# Sensors_Actuator_lib.net
KiCad netlist of a schematic drawn in Altium Designer
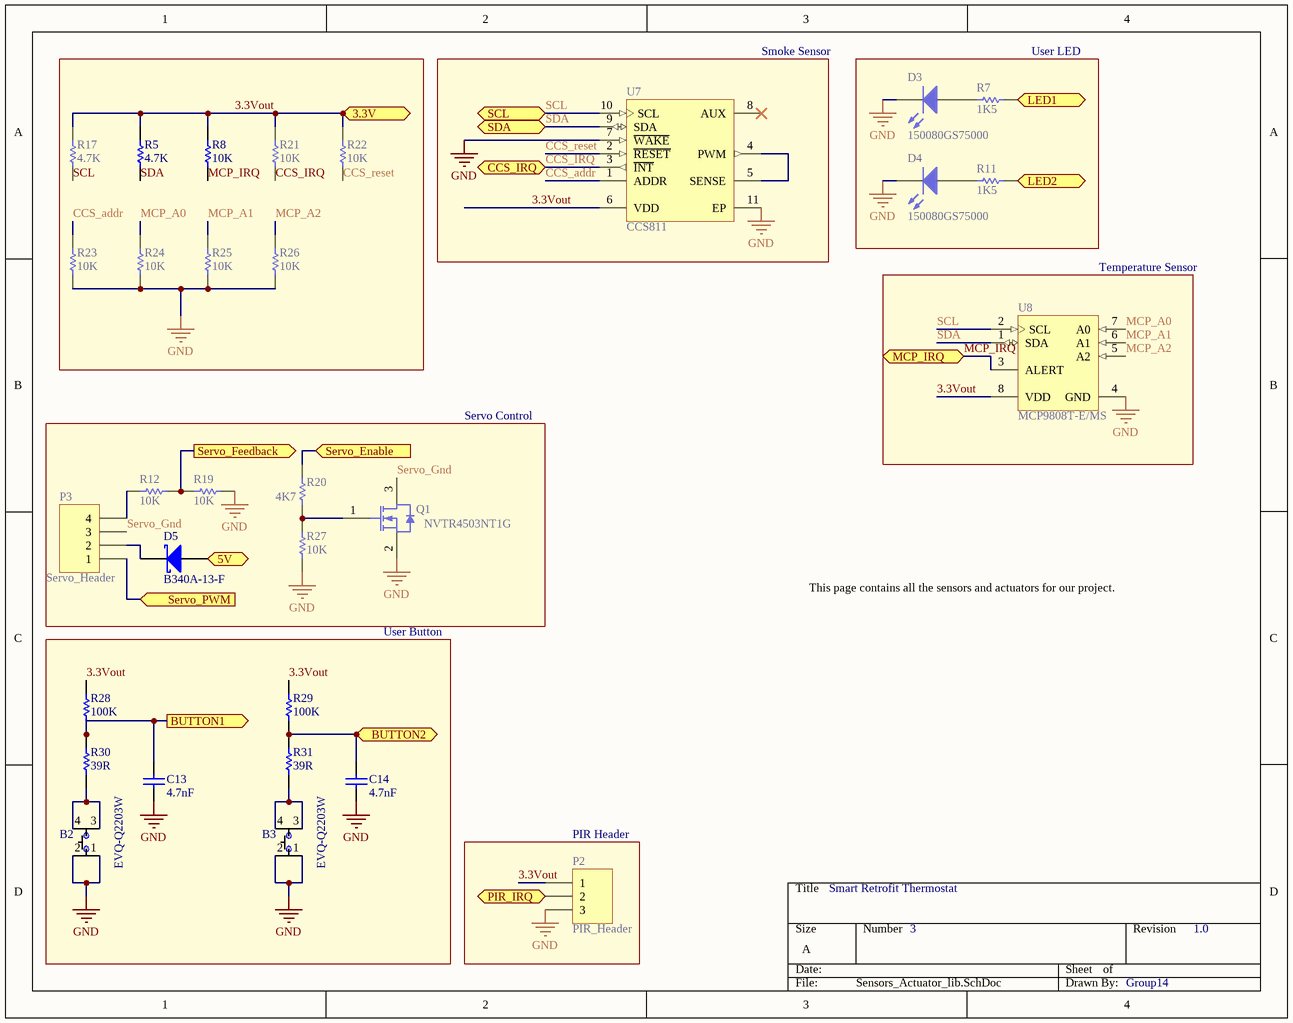
[diagram p0: Sensors_Actuator_lib.SchDoc]

(export (version "E")
  (design (tool "Eeschema 10.0.6"))
  (components
    (comp (ref "B2")
      (value "EVQ-Q2203W")
      (footprint "EVQ-Q2203W")
      (description "SWITCH TACTILE SPST-NO 0.02A 15V")
      (fields (field (name "MANUFACTURER") "Panasonic Electronic Components"))
      (libsource (lib "ese516_baseComponents") (part "EVQ-Q2203W"))
    )
    (comp (ref "B3")
      (value "EVQ-Q2203W")
      (footprint "EVQ-Q2203W")
      (description "SWITCH TACTILE SPST-NO 0.02A 15V")
      (fields (field (name "MANUFACTURER") "Panasonic Electronic Components"))
      (libsource (lib "ese516_baseComponents") (part "EVQ-Q2203W"))
    )
    (comp (ref "C13")
      (value "4.7nF")
      (footprint "CAPC0805(2012)100_L")
      (description "CAP 4.7nF 16V ±20% 0805 (2012 Metric) Thickness 1mm SMD")
      (fields (field (name "TOLERANCE") "Â±20%"))
      (libsource (lib "Altium Content Vault") (part "CAP"))
    )
    (comp (ref "C14")
      (value "4.7nF")
      (footprint "CAPC0805(2012)100_L")
      (description "CAP 4.7nF 16V ±20% 0805 (2012 Metric) Thickness 1mm SMD")
      (fields (field (name "TOLERANCE") "Â±20%"))
      (libsource (lib "Altium Content Vault") (part "CAP"))
    )
    (comp (ref "D3")
      (value "150080GS75000")
      (footprint "0805_A")
      (description "SMD mono-color Chip LED, WL-SMCW, Green")
      (fields (field (name "MANUFACTURER") "Wuerth Elektronik"))
      (libsource (lib "Altium Content Vault") (part "WE-LED_K1A2-2"))
    )
    (comp (ref "D4")
      (value "150080GS75000")
      (footprint "0805_A")
      (description "SMD mono-color Chip LED, WL-SMCW, Green")
      (fields (field (name "MANUFACTURER") "Wuerth Elektronik"))
      (libsource (lib "Altium Content Vault") (part "WE-LED_K1A2-2"))
    )
    (comp (ref "D5")
      (value "B340A-13-F")
      (footprint "DIOD-SMA-2_V")
      (libsource (lib "Altium Content Vault") (part "DSKY-AK-2"))
    )
    (comp (ref "P2")
      (value "PIR_Header")
      (footprint "HDR1X3")
      (description "Header, 3-Pin")
      (fields (field (name "PUBLISHER") "Altium Limited"))
      (libsource (lib "Miscellaneous Connectors") (part "Header 3"))
    )
    (comp (ref "P3")
      (value "Servo_Header")
      (footprint "HDR1X4")
      (description "Header, 4-Pin")
      (fields (field (name "PUBLISHER") "Altium Limited"))
      (libsource (lib "Miscellaneous Connectors") (part "Header 4"))
    )
    (comp (ref "Q1")
      (value "NVTR4503NT1G")
      (footprint "ONSC-SOT-23-3-318-08_V")
      (description "Power MOSFET, 30 V, 2.5 A, Single N-Channel, 3-Pin SOT-23, Pb-Free, Tape and Reel")
      (fields (field (name "MANUFACTURER") "On Semiconductor"))
      (libsource (lib "Altium Content Vault") (part "ONSC-NMOS-G1S2D3-3"))
    )
    (comp (ref "R5")
      (value "4.7K")
      (footprint "RESC2113X50X35ML15T15")
      (description "Chip Resistor, 4.7 KOhm, +/- 1%, 0.125 W, -55 to 155 degC, 0805 (2012 Metric), RoHS, Tape and Reel")
      (fields (field (name "TOLERANCE") "1%") (field (name "MANUFACTURER") "Vishay Semiconductor"))
      (libsource (lib "Altium Content Vault") (part "CMP-2100-03615-1"))
    )
    (comp (ref "R7")
      (value "1K5")
      (footprint "RESC0805(2012)_M")
      (description "1K5 0.125W 1% 0805 (2012 Metric)  SMD")
      (fields (field (name "POWER") "0.125 W") (field (name "TOLERANCE") "1 %"))
      (libsource (lib "Altium Content Vault") (part "CMP-1013-00528-1"))
    )
    (comp (ref "R8")
      (value "10K")
      (footprint "RESC0805(2012)_M")
      (description "10K 0.125W 1% 0805 (2012 Metric)  SMD")
      (fields (field (name "POWER") "0.125 W") (field (name "TOLERANCE") "1 %"))
      (libsource (lib "Altium Content Vault") (part "RES"))
    )
    (comp (ref "R11")
      (value "1K5")
      (footprint "RESC0805(2012)_M")
      (description "1K5 0.125W 1% 0805 (2012 Metric)  SMD")
      (fields (field (name "POWER") "0.125 W") (field (name "TOLERANCE") "1 %"))
      (libsource (lib "Altium Content Vault") (part "RES"))
    )
    (comp (ref "R12")
      (value "10K")
      (footprint "RESC0805(2012)_M")
      (description "10K 0.125W 1% 0805 (2012 Metric)  SMD")
      (fields (field (name "POWER") "0.125 W") (field (name "TOLERANCE") "1 %"))
      (libsource (lib "Altium Content Vault") (part "RES"))
    )
    (comp (ref "R17")
      (value "4.7K")
      (footprint "RESC2113X50X35ML15T15")
      (description "Chip Resistor, 4.7 KOhm, +/- 1%, 0.125 W, -55 to 155 degC, 0805 (2012 Metric), RoHS, Tape and Reel")
      (fields (field (name "TOLERANCE") "1%") (field (name "MANUFACTURER") "Vishay Semiconductor"))
      (libsource (lib "Altium Content Vault") (part "CMP-2100-03615-1"))
    )
    (comp (ref "R19")
      (value "10K")
      (footprint "RESC0805(2012)_M")
      (description "10K 0.125W 1% 0805 (2012 Metric)  SMD")
      (fields (field (name "POWER") "0.125 W") (field (name "TOLERANCE") "1 %"))
      (libsource (lib "Altium Content Vault") (part "RES"))
    )
    (comp (ref "R20")
      (value "4K7")
      (footprint "RESC0805(2012)_M")
      (description "4K7 0.125W 1% 0805 (2012 Metric)  SMD")
      (fields (field (name "POWER") "0.125 W") (field (name "TOLERANCE") "1 %"))
      (libsource (lib "Altium Content Vault") (part "RES"))
    )
    (comp (ref "R21")
      (value "10K")
      (footprint "RESC0805(2012)_M")
      (description "10K 0.125W 1% 0805 (2012 Metric)  SMD")
      (fields (field (name "POWER") "0.125 W") (field (name "TOLERANCE") "1 %"))
      (libsource (lib "Altium Content Vault") (part "RES"))
    )
    (comp (ref "R22")
      (value "10K")
      (footprint "RESC0805(2012)_M")
      (description "10K 0.125W 1% 0805 (2012 Metric)  SMD")
      (fields (field (name "POWER") "0.125 W") (field (name "TOLERANCE") "1 %"))
      (libsource (lib "Altium Content Vault") (part "RES"))
    )
    (comp (ref "R23")
      (value "10K")
      (footprint "RESC0805(2012)_M")
      (description "10K 0.125W 1% 0805 (2012 Metric)  SMD")
      (fields (field (name "POWER") "0.125 W") (field (name "TOLERANCE") "1 %"))
      (libsource (lib "Altium Content Vault") (part "RES"))
    )
    (comp (ref "R24")
      (value "10K")
      (footprint "RESC0805(2012)_M")
      (description "10K 0.125W 1% 0805 (2012 Metric)  SMD")
      (fields (field (name "POWER") "0.125 W") (field (name "TOLERANCE") "1 %"))
      (libsource (lib "Altium Content Vault") (part "RES"))
    )
    (comp (ref "R25")
      (value "10K")
      (footprint "RESC0805(2012)_M")
      (description "10K 0.125W 1% 0805 (2012 Metric)  SMD")
      (fields (field (name "POWER") "0.125 W") (field (name "TOLERANCE") "1 %"))
      (libsource (lib "Altium Content Vault") (part "RES"))
    )
    (comp (ref "R26")
      (value "10K")
      (footprint "RESC0805(2012)_M")
      (description "10K 0.125W 1% 0805 (2012 Metric)  SMD")
      (fields (field (name "POWER") "0.125 W") (field (name "TOLERANCE") "1 %"))
      (libsource (lib "Altium Content Vault") (part "RES"))
    )
    (comp (ref "R27")
      (value "10K")
      (footprint "RESC0805(2012)_M")
      (description "10K 0.125W 1% 0805 (2012 Metric)  SMD")
      (fields (field (name "POWER") "0.125 W") (field (name "TOLERANCE") "1 %"))
      (libsource (lib "Altium Content Vault") (part "RES"))
    )
    (comp (ref "R28")
      (value "100K")
      (footprint "RESC0805(2012)_L")
      (description "100K 0.125W 1% 0805 (2012 Metric)  SMD")
      (fields (field (name "POWER") "0.125 W") (field (name "TOLERANCE") "1 %"))
      (libsource (lib "Altium Content Vault") (part "RES"))
    )
    (comp (ref "R29")
      (value "100K")
      (footprint "RESC0805(2012)_L")
      (description "100K 0.125W 1% 0805 (2012 Metric)  SMD")
      (fields (field (name "POWER") "0.125 W") (field (name "TOLERANCE") "1 %"))
      (libsource (lib "Altium Content Vault") (part "RES"))
    )
    (comp (ref "R30")
      (value "39R")
      (footprint "RESC0805(2012)_N")
      (description "39R 0.125W 1% 0805 (2012 Metric)  SMD")
      (fields (field (name "POWER") "0.125 W") (field (name "TOLERANCE") "1 %"))
      (libsource (lib "Altium Content Vault") (part "RES"))
    )
    (comp (ref "R31")
      (value "39R")
      (footprint "RESC0805(2012)_N")
      (description "39R 0.125W 1% 0805 (2012 Metric)  SMD")
      (fields (field (name "POWER") "0.125 W") (field (name "TOLERANCE") "1 %"))
      (libsource (lib "Altium Content Vault") (part "RES"))
    )
    (comp (ref "U7")
      (value "CCS811")
      (footprint "AMS-LGA-10_V")
      (fields (field (name "MANUFACTURER") "AMS"))
      (libsource (lib "Altium Content Vault") (part "CMP-2000-07443-1"))
    )
    (comp (ref "U8")
      (value "MCP9808T-E/MS")
      (footprint "MCHP-MSOP-MS8_M")
      (fields (field (name "MANUFACTURER") "Microchip"))
      (libsource (lib "Altium Content Vault") (part "MCHP-MCP9808-MSOP-8"))
    )
  )
  (nets
    (net (code "1") (name "/3.3Vout") (class "Default")
      (node (ref "P2") (pin "1") (pinfunction "1_1") (pintype "passive"))
      (node (ref "R17") (pin "2") (pinfunction "2_2") (pintype "passive"))
      (node (ref "R21") (pin "2") (pinfunction "2_2") (pintype "passive"))
      (node (ref "R22") (pin "2") (pinfunction "2_2") (pintype "passive"))
      (node (ref "R28") (pin "1") (pinfunction "1_1") (pintype "passive"))
      (node (ref "R29") (pin "1") (pinfunction "1_1") (pintype "passive"))
      (node (ref "R5") (pin "2") (pinfunction "2_2") (pintype "passive"))
      (node (ref "R8") (pin "2") (pinfunction "2_2") (pintype "passive"))
      (node (ref "U7") (pin "6") (pinfunction "VDD_6") (pintype "power_in"))
      (node (ref "U8") (pin "8") (pinfunction "VDD_8") (pintype "power_in"))
    )
    (net (code "2") (name "/5V") (class "Default")
      (node (ref "D5") (pin "1") (pinfunction "A_1") (pintype "passive"))
    )
    (net (code "3") (name "/BUTTON1") (class "Default")
      (node (ref "C13") (pin "2") (pinfunction "2_2") (pintype "passive"))
      (node (ref "R28") (pin "2") (pinfunction "2_2") (pintype "passive"))
      (node (ref "R30") (pin "1") (pinfunction "1_1") (pintype "passive"))
    )
    (net (code "4") (name "/BUTTON2") (class "Default")
      (node (ref "C14") (pin "2") (pinfunction "2_2") (pintype "passive"))
      (node (ref "R29") (pin "2") (pinfunction "2_2") (pintype "passive"))
      (node (ref "R31") (pin "1") (pinfunction "1_1") (pintype "passive"))
    )
    (net (code "5") (name "/CCS_IRQ") (class "Default")
      (node (ref "R21") (pin "1") (pinfunction "1_1") (pintype "passive"))
      (node (ref "U7") (pin "3") (pinfunction "~{INT}_3") (pintype "output"))
    )
    (net (code "6") (name "/CCS_addr") (class "Default")
      (node (ref "R23") (pin "2") (pinfunction "2_2") (pintype "passive"))
      (node (ref "U7") (pin "1") (pinfunction "ADDR_1") (pintype "passive"))
    )
    (net (code "7") (name "/CCS_reset") (class "Default")
      (node (ref "R22") (pin "1") (pinfunction "1_1") (pintype "passive"))
      (node (ref "U7") (pin "2") (pinfunction "~{RESET}_2") (pintype "input"))
    )
    (net (code "8") (name "/LED1") (class "Default")
      (node (ref "R7") (pin "2") (pinfunction "2_2") (pintype "passive"))
    )
    (net (code "9") (name "/LED2") (class "Default")
      (node (ref "R11") (pin "2") (pinfunction "2_2") (pintype "passive"))
    )
    (net (code "10") (name "/MCP_A0") (class "Default")
      (node (ref "R24") (pin "2") (pinfunction "2_2") (pintype "passive"))
      (node (ref "U8") (pin "7") (pinfunction "A0_7") (pintype "input"))
    )
    (net (code "11") (name "/MCP_A1") (class "Default")
      (node (ref "R25") (pin "2") (pinfunction "2_2") (pintype "passive"))
      (node (ref "U8") (pin "6") (pinfunction "A1_6") (pintype "input"))
    )
    (net (code "12") (name "/MCP_A2") (class "Default")
      (node (ref "R26") (pin "2") (pinfunction "2_2") (pintype "passive"))
      (node (ref "U8") (pin "5") (pinfunction "A2_5") (pintype "input"))
    )
    (net (code "13") (name "/MCP_IRQ") (class "Default")
      (node (ref "R8") (pin "1") (pinfunction "1_1") (pintype "passive"))
      (node (ref "U8") (pin "3") (pinfunction "ALERT_3") (pintype "open_collector"))
    )
    (net (code "14") (name "/PIR_IRQ") (class "Default")
      (node (ref "P2") (pin "2") (pinfunction "2_2") (pintype "passive"))
    )
    (net (code "15") (name "/SCL") (class "Default")
      (node (ref "R17") (pin "1") (pinfunction "1_1") (pintype "passive"))
      (node (ref "U7") (pin "10") (pinfunction "SCL_10") (pintype "input"))
      (node (ref "U8") (pin "2") (pinfunction "SCL_2") (pintype "input"))
    )
    (net (code "16") (name "/SDA") (class "Default")
      (node (ref "R5") (pin "1") (pinfunction "1_1") (pintype "passive"))
      (node (ref "U7") (pin "9") (pinfunction "SDA_9") (pintype "bidirectional"))
      (node (ref "U8") (pin "1") (pinfunction "SDA_1") (pintype "bidirectional"))
    )
    (net (code "17") (name "/Servo_Enable") (class "Default")
      (node (ref "R20") (pin "2") (pinfunction "2_2") (pintype "passive"))
    )
    (net (code "18") (name "/Servo_Feedback") (class "Default")
      (node (ref "R12") (pin "1") (pinfunction "1_1") (pintype "passive"))
      (node (ref "R19") (pin "2") (pinfunction "2_2") (pintype "passive"))
    )
    (net (code "19") (name "/Servo_Gnd") (class "Default")
      (node (ref "P3") (pin "3") (pinfunction "3_3") (pintype "passive"))
      (node (ref "Q1") (pin "3") (pinfunction "D_3") (pintype "passive"))
    )
    (net (code "20") (name "/Servo_PWM") (class "Default")
      (node (ref "P3") (pin "1") (pinfunction "1_1") (pintype "passive"))
    )
    (net (code "21") (name "GND") (class "Default")
      (node (ref "B2") (pin "1") (pinfunction "1_1") (pintype "power_in"))
      (node (ref "B2") (pin "2") (pinfunction "2_2") (pintype "power_in"))
      (node (ref "B3") (pin "1") (pinfunction "1_1") (pintype "power_in"))
      (node (ref "B3") (pin "2") (pinfunction "2_2") (pintype "power_in"))
      (node (ref "C13") (pin "1") (pinfunction "1_1") (pintype "passive"))
      (node (ref "C14") (pin "1") (pinfunction "1_1") (pintype "passive"))
      (node (ref "D3") (pin "1") (pinfunction "K_1") (pintype "passive"))
      (node (ref "D4") (pin "1") (pinfunction "K_1") (pintype "passive"))
      (node (ref "P2") (pin "3") (pinfunction "3_3") (pintype "passive"))
      (node (ref "Q1") (pin "2") (pinfunction "S_2") (pintype "passive"))
      (node (ref "R19") (pin "1") (pinfunction "1_1") (pintype "passive"))
      (node (ref "R23") (pin "1") (pinfunction "1_1") (pintype "passive"))
      (node (ref "R24") (pin "1") (pinfunction "1_1") (pintype "passive"))
      (node (ref "R25") (pin "1") (pinfunction "1_1") (pintype "passive"))
      (node (ref "R26") (pin "1") (pinfunction "1_1") (pintype "passive"))
      (node (ref "R27") (pin "1") (pinfunction "1_1") (pintype "passive"))
      (node (ref "U7") (pin "11") (pinfunction "EP_11") (pintype "power_in"))
      (node (ref "U7") (pin "7") (pinfunction "~{WAKE}_7") (pintype "input"))
      (node (ref "U8") (pin "4") (pinfunction "GND_4") (pintype "power_in"))
    )
    (net (code "22") (name "Net-(B2-Pad3)") (class "Default")
      (node (ref "B2") (pin "3") (pinfunction "3_3") (pintype "power_in"))
      (node (ref "B2") (pin "4") (pinfunction "4_4") (pintype "power_in"))
      (node (ref "R30") (pin "2") (pinfunction "2_2") (pintype "passive"))
    )
    (net (code "23") (name "Net-(B3-Pad3)") (class "Default")
      (node (ref "B3") (pin "3") (pinfunction "3_3") (pintype "power_in"))
      (node (ref "B3") (pin "4") (pinfunction "4_4") (pintype "power_in"))
      (node (ref "R31") (pin "2") (pinfunction "2_2") (pintype "passive"))
    )
    (net (code "24") (name "Net-(D3-A)") (class "Default")
      (node (ref "D3") (pin "2") (pinfunction "A_2") (pintype "passive"))
      (node (ref "R7") (pin "1") (pinfunction "1_1") (pintype "passive"))
    )
    (net (code "25") (name "Net-(D4-A)") (class "Default")
      (node (ref "D4") (pin "2") (pinfunction "A_2") (pintype "passive"))
      (node (ref "R11") (pin "1") (pinfunction "1_1") (pintype "passive"))
    )
    (net (code "26") (name "Net-(D5-K)") (class "Default")
      (node (ref "D5") (pin "2") (pinfunction "K_2") (pintype "passive"))
      (node (ref "P3") (pin "2") (pinfunction "2_2") (pintype "passive"))
    )
    (net (code "27") (name "Net-(P3-Pad4)") (class "Default")
      (node (ref "P3") (pin "4") (pinfunction "4_4") (pintype "passive"))
      (node (ref "R12") (pin "2") (pinfunction "2_2") (pintype "passive"))
    )
    (net (code "28") (name "Net-(Q1-G)") (class "Default")
      (node (ref "Q1") (pin "1") (pinfunction "G_1") (pintype "passive"))
      (node (ref "R20") (pin "1") (pinfunction "1_1") (pintype "passive"))
      (node (ref "R27") (pin "2") (pinfunction "2_2") (pintype "passive"))
    )
    (net (code "29") (name "Net-(U7-PWM)") (class "Default")
      (node (ref "U7") (pin "4") (pinfunction "PWM_4") (pintype "output"))
      (node (ref "U7") (pin "5") (pinfunction "SENSE_5") (pintype "passive"))
    )
    (net (code "30") (name "unconnected-(U7-AUX-Pad8)") (class "Default")
      (node (ref "U7") (pin "8") (pinfunction "AUX_8") (pintype "passive+no_connect"))
    )
  )
)
